# Amplifiers.net
KiCad netlist of a schematic drawn in Altium Designer
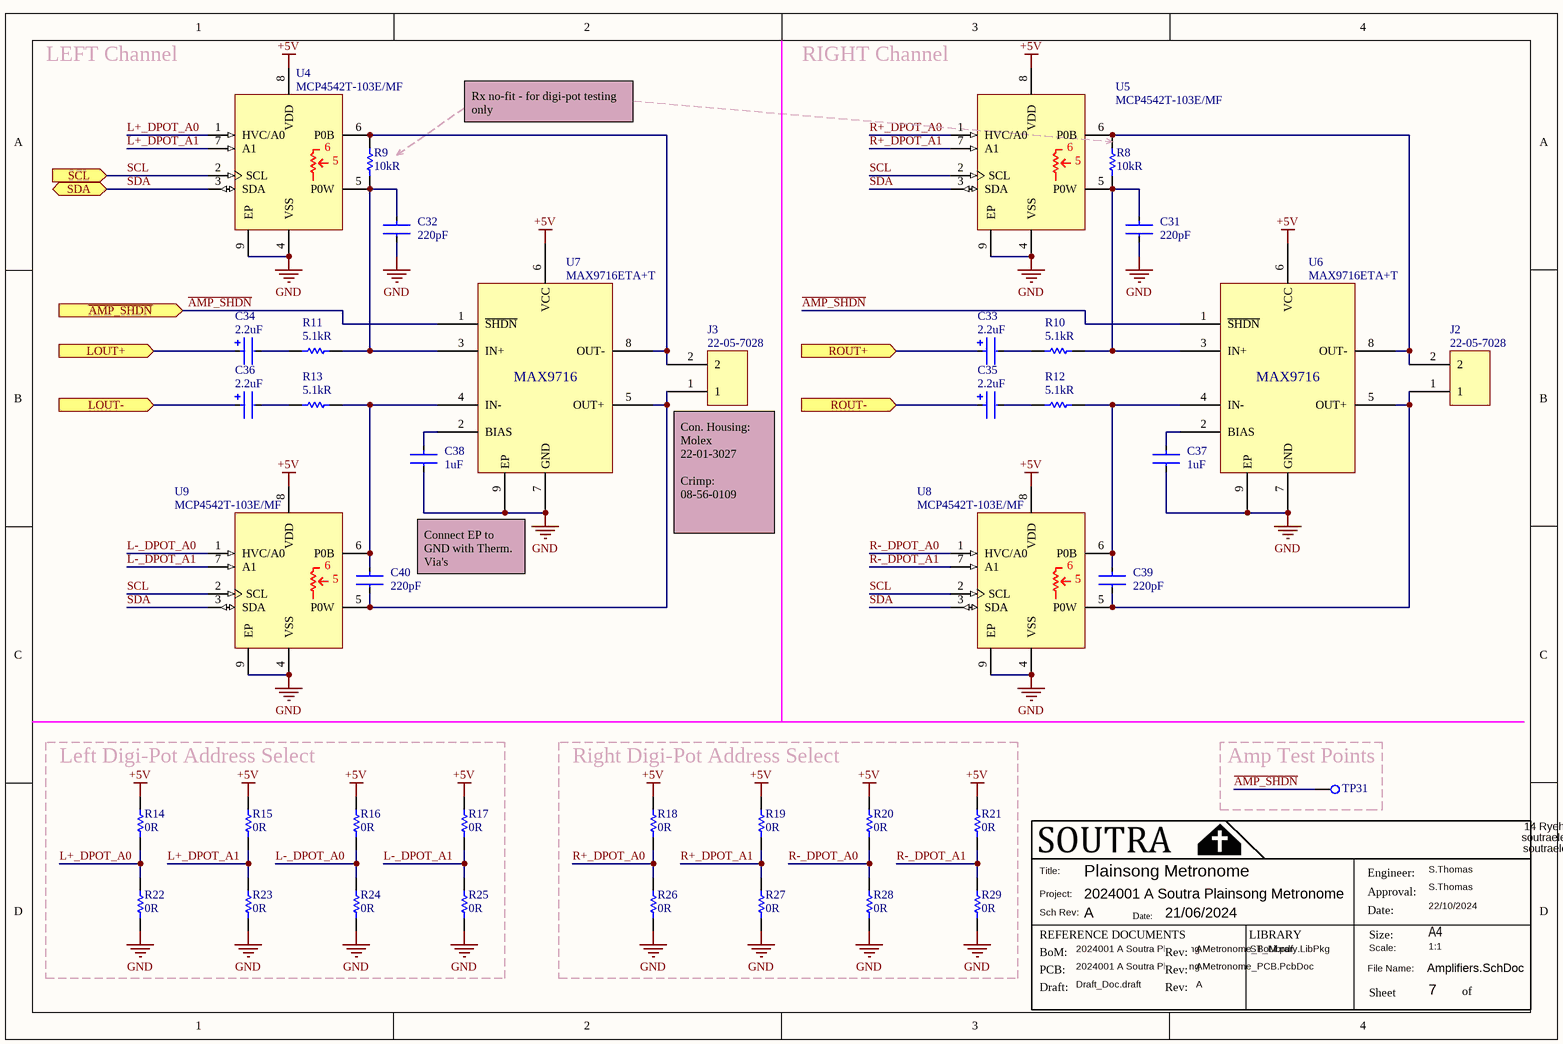
[diagram p0: Amplifiers.SchDoc]

(export (version "E")
  (design (tool "Eeschema 10.0.6"))
  (components
    (comp (ref "C31")
      (value "220pF")
      (footprint "CAPC1005X06L")
      (fields
        (field (name "MANUFACTURER") "Yageo")
        (field (name "MANUFACTURER PART NUMBER") "CC0402KPX7R9BB221")
        (field (name "ALTERNATIVE PART") "MC0402B221K500CT")
      )
      (libsource (lib "ST_Library") (part "CC0402KPX7R9BB221"))
    )
    (comp (ref "C32")
      (value "220pF")
      (footprint "CAPC1005X06L")
      (fields
        (field (name "MANUFACTURER") "Yageo")
        (field (name "MANUFACTURER PART NUMBER") "CC0402KPX7R9BB221")
        (field (name "ALTERNATIVE PART") "MC0402B221K500CT")
      )
      (libsource (lib "ST_Library") (part "CC0402KPX7R9BB221"))
    )
    (comp (ref "C33")
      (value "2.2uF")
      (footprint "CAPC2113X120X50ML20T30")
      (description "Surface Mount Tantalum Capacitor, 2.2 µF, 16 V, 0805 [2012 Metric], ± 10%, 6.5 ohm, R")
      (fields
        (field (name "MANUFACTURER") "AVX Interconnect / Elco")
        (field (name "PART NUMBER") "TAJR225K016RNJ")
      )
      (libsource (lib "ST_Library") (part "TAJR225K016RNJ"))
    )
    (comp (ref "C34")
      (value "2.2uF")
      (footprint "CAPC2113X120X50ML20T30")
      (description "Surface Mount Tantalum Capacitor, 2.2 µF, 16 V, 0805 [2012 Metric], ± 10%, 6.5 ohm, R")
      (fields
        (field (name "MANUFACTURER") "AVX Interconnect / Elco")
        (field (name "PART NUMBER") "TAJR225K016RNJ")
      )
      (libsource (lib "ST_Library") (part "TAJR225K016RNJ"))
    )
    (comp (ref "C35")
      (value "2.2uF")
      (footprint "CAPC2113X120X50ML20T30")
      (description "Surface Mount Tantalum Capacitor, 2.2 µF, 16 V, 0805 [2012 Metric], ± 10%, 6.5 ohm, R")
      (fields
        (field (name "MANUFACTURER") "AVX Interconnect / Elco")
        (field (name "PART NUMBER") "TAJR225K016RNJ")
      )
      (libsource (lib "ST_Library") (part "TAJR225K016RNJ"))
    )
    (comp (ref "C36")
      (value "2.2uF")
      (footprint "CAPC2113X120X50ML20T30")
      (description "Surface Mount Tantalum Capacitor, 2.2 µF, 16 V, 0805 [2012 Metric], ± 10%, 6.5 ohm, R")
      (fields
        (field (name "MANUFACTURER") "AVX Interconnect / Elco")
        (field (name "PART NUMBER") "TAJR225K016RNJ")
      )
      (libsource (lib "ST_Library") (part "TAJR225K016RNJ"))
    )
    (comp (ref "C37")
      (value "1uF")
      (footprint "CAPC1005X06L")
      (fields
        (field (name "MANUFACTURER") "Yageo")
        (field (name "MANUFACTURER PART NUMBER") "CC0402KRX5R6BB105")
        (field (name "ALTERNATIVE PART") "0402ZD105KAT2A")
      )
      (libsource (lib "ST_Library") (part "CC0402KRX5R6BB105"))
    )
    (comp (ref "C38")
      (value "1uF")
      (footprint "CAPC1005X06L")
      (fields
        (field (name "MANUFACTURER") "Yageo")
        (field (name "MANUFACTURER PART NUMBER") "CC0402KRX5R6BB105")
        (field (name "ALTERNATIVE PART") "0402ZD105KAT2A")
      )
      (libsource (lib "ST_Library") (part "CC0402KRX5R6BB105"))
    )
    (comp (ref "C39")
      (value "220pF")
      (footprint "CAPC1005X06L")
      (fields
        (field (name "MANUFACTURER") "Yageo")
        (field (name "MANUFACTURER PART NUMBER") "CC0402KPX7R9BB221")
        (field (name "ALTERNATIVE PART") "MC0402B221K500CT")
      )
      (libsource (lib "ST_Library") (part "CC0402KPX7R9BB221"))
    )
    (comp (ref "C40")
      (value "220pF")
      (footprint "CAPC1005X06L")
      (fields
        (field (name "MANUFACTURER") "Yageo")
        (field (name "MANUFACTURER PART NUMBER") "CC0402KPX7R9BB221")
        (field (name "ALTERNATIVE PART") "MC0402B221K500CT")
      )
      (libsource (lib "ST_Library") (part "CC0402KPX7R9BB221"))
    )
    (comp (ref "J2")
      (value "22-05-7028")
      (footprint "J_MOLEX_22-05-7028")
      (fields (field (name "MANUFACTURER") "Molex"))
      (libsource (lib "ST_Library") (part "22-05-7028"))
    )
    (comp (ref "J3")
      (value "22-05-7028")
      (footprint "J_MOLEX_22-05-7028")
      (fields (field (name "MANUFACTURER") "Molex"))
      (libsource (lib "ST_Library") (part "22-05-7028"))
    )
    (comp (ref "R8")
      (value "10kR")
      (footprint "RESC_0805_2013X50X30LL20T20")
      (fields
        (field (name "MANUFACTURER") "Yageo")
        (field (name "MANUFACTURER PART NUMBER") "RC0805JR-0710KL")
        (field (name "TOLERANCE") "5%")
      )
      (libsource (lib "ST_Library") (part "RC0805JR-0710KL"))
    )
    (comp (ref "R9")
      (value "10kR")
      (footprint "RESC_0805_2013X50X30LL20T20")
      (fields
        (field (name "MANUFACTURER") "Yageo")
        (field (name "MANUFACTURER PART NUMBER") "RC0805JR-0710KL")
        (field (name "TOLERANCE") "5%")
      )
      (libsource (lib "ST_Library") (part "RC0805JR-0710KL"))
    )
    (comp (ref "R10")
      (value "5.1kR")
      (footprint "RESC_0603_1608X06L")
      (description "Fixed Resistor, 0.1W, 5100ohm, 75V, 5% +/-Tol, 100ppm/Cel, Surface Mount, 0603")
      (fields
        (field (name "MANUFACTURER") "Multicomp")
        (field (name "MANUFACTURER PART NUMBER") "MCMR06X512JTL")
      )
      (libsource (lib "ST_Library") (part "MCMR06X512JTL"))
    )
    (comp (ref "R11")
      (value "5.1kR")
      (footprint "RESC_0603_1608X06L")
      (description "Fixed Resistor, 0.1W, 5100ohm, 75V, 5% +/-Tol, 100ppm/Cel, Surface Mount, 0603")
      (fields
        (field (name "MANUFACTURER") "Multicomp")
        (field (name "MANUFACTURER PART NUMBER") "MCMR06X512JTL")
      )
      (libsource (lib "ST_Library") (part "MCMR06X512JTL"))
    )
    (comp (ref "R12")
      (value "5.1kR")
      (footprint "RESC_0603_1608X06L")
      (description "Fixed Resistor, 0.1W, 5100ohm, 75V, 5% +/-Tol, 100ppm/Cel, Surface Mount, 0603")
      (fields
        (field (name "MANUFACTURER") "Multicomp")
        (field (name "MANUFACTURER PART NUMBER") "MCMR06X512JTL")
      )
      (libsource (lib "ST_Library") (part "MCMR06X512JTL"))
    )
    (comp (ref "R13")
      (value "5.1kR")
      (footprint "RESC_0603_1608X06L")
      (description "Fixed Resistor, 0.1W, 5100ohm, 75V, 5% +/-Tol, 100ppm/Cel, Surface Mount, 0603")
      (fields
        (field (name "MANUFACTURER") "Multicomp")
        (field (name "MANUFACTURER PART NUMBER") "MCMR06X512JTL")
      )
      (libsource (lib "ST_Library") (part "MCMR06X512JTL"))
    )
    (comp (ref "R14")
      (value "0R")
      (footprint "RESC_0603_1608X06L")
      (description "Fixed Resistor, Metal Glaze/thick Film, 0.063W, 0ohm, 1% +/-Tol, Surface Mount, 0603")
      (fields
        (field (name "MANUFACTURER") "Multicomp")
        (field (name "MANUFACTURER PART NUMBER") "MC0063W06030R")
      )
      (libsource (lib "ST_Library") (part "MC0063W06030R"))
    )
    (comp (ref "R15")
      (value "0R")
      (footprint "RESC_0603_1608X06L")
      (description "Fixed Resistor, Metal Glaze/thick Film, 0.063W, 0ohm, 1% +/-Tol, Surface Mount, 0603")
      (fields
        (field (name "MANUFACTURER") "Multicomp")
        (field (name "MANUFACTURER PART NUMBER") "MC0063W06030R")
      )
      (libsource (lib "ST_Library") (part "MC0063W06030R"))
    )
    (comp (ref "R16")
      (value "0R")
      (footprint "RESC_0603_1608X06L")
      (description "Fixed Resistor, Metal Glaze/thick Film, 0.063W, 0ohm, 1% +/-Tol, Surface Mount, 0603")
      (fields
        (field (name "MANUFACTURER") "Multicomp")
        (field (name "MANUFACTURER PART NUMBER") "MC0063W06030R")
      )
      (libsource (lib "ST_Library") (part "MC0063W06030R"))
    )
    (comp (ref "R17")
      (value "0R")
      (footprint "RESC_0603_1608X06L")
      (description "Fixed Resistor, Metal Glaze/thick Film, 0.063W, 0ohm, 1% +/-Tol, Surface Mount, 0603")
      (fields
        (field (name "MANUFACTURER") "Multicomp")
        (field (name "MANUFACTURER PART NUMBER") "MC0063W06030R")
      )
      (libsource (lib "ST_Library") (part "MC0063W06030R"))
    )
    (comp (ref "R18")
      (value "0R")
      (footprint "RESC_0603_1608X06L")
      (description "Fixed Resistor, Metal Glaze/thick Film, 0.063W, 0ohm, 1% +/-Tol, Surface Mount, 0603")
      (fields
        (field (name "MANUFACTURER") "Multicomp")
        (field (name "MANUFACTURER PART NUMBER") "MC0063W06030R")
      )
      (libsource (lib "ST_Library") (part "MC0063W06030R"))
    )
    (comp (ref "R19")
      (value "0R")
      (footprint "RESC_0603_1608X06L")
      (description "Fixed Resistor, Metal Glaze/thick Film, 0.063W, 0ohm, 1% +/-Tol, Surface Mount, 0603")
      (fields
        (field (name "MANUFACTURER") "Multicomp")
        (field (name "MANUFACTURER PART NUMBER") "MC0063W06030R")
      )
      (libsource (lib "ST_Library") (part "MC0063W06030R"))
    )
    (comp (ref "R20")
      (value "0R")
      (footprint "RESC_0603_1608X06L")
      (description "Fixed Resistor, Metal Glaze/thick Film, 0.063W, 0ohm, 1% +/-Tol, Surface Mount, 0603")
      (fields
        (field (name "MANUFACTURER") "Multicomp")
        (field (name "MANUFACTURER PART NUMBER") "MC0063W06030R")
      )
      (libsource (lib "ST_Library") (part "MC0063W06030R"))
    )
    (comp (ref "R21")
      (value "0R")
      (footprint "RESC_0603_1608X06L")
      (description "Fixed Resistor, Metal Glaze/thick Film, 0.063W, 0ohm, 1% +/-Tol, Surface Mount, 0603")
      (fields
        (field (name "MANUFACTURER") "Multicomp")
        (field (name "MANUFACTURER PART NUMBER") "MC0063W06030R")
      )
      (libsource (lib "ST_Library") (part "MC0063W06030R"))
    )
    (comp (ref "R22")
      (value "0R")
      (footprint "RESC_0603_1608X06L")
      (description "Fixed Resistor, Metal Glaze/thick Film, 0.063W, 0ohm, 1% +/-Tol, Surface Mount, 0603")
      (fields
        (field (name "MANUFACTURER") "Multicomp")
        (field (name "MANUFACTURER PART NUMBER") "MC0063W06030R")
      )
      (libsource (lib "ST_Library") (part "MC0063W06030R"))
    )
    (comp (ref "R23")
      (value "0R")
      (footprint "RESC_0603_1608X06L")
      (description "Fixed Resistor, Metal Glaze/thick Film, 0.063W, 0ohm, 1% +/-Tol, Surface Mount, 0603")
      (fields
        (field (name "MANUFACTURER") "Multicomp")
        (field (name "MANUFACTURER PART NUMBER") "MC0063W06030R")
      )
      (libsource (lib "ST_Library") (part "MC0063W06030R"))
    )
    (comp (ref "R24")
      (value "0R")
      (footprint "RESC_0603_1608X06L")
      (description "Fixed Resistor, Metal Glaze/thick Film, 0.063W, 0ohm, 1% +/-Tol, Surface Mount, 0603")
      (fields
        (field (name "MANUFACTURER") "Multicomp")
        (field (name "MANUFACTURER PART NUMBER") "MC0063W06030R")
      )
      (libsource (lib "ST_Library") (part "MC0063W06030R"))
    )
    (comp (ref "R25")
      (value "0R")
      (footprint "RESC_0603_1608X06L")
      (description "Fixed Resistor, Metal Glaze/thick Film, 0.063W, 0ohm, 1% +/-Tol, Surface Mount, 0603")
      (fields
        (field (name "MANUFACTURER") "Multicomp")
        (field (name "MANUFACTURER PART NUMBER") "MC0063W06030R")
      )
      (libsource (lib "ST_Library") (part "MC0063W06030R"))
    )
    (comp (ref "R26")
      (value "0R")
      (footprint "RESC_0603_1608X06L")
      (description "Fixed Resistor, Metal Glaze/thick Film, 0.063W, 0ohm, 1% +/-Tol, Surface Mount, 0603")
      (fields
        (field (name "MANUFACTURER") "Multicomp")
        (field (name "MANUFACTURER PART NUMBER") "MC0063W06030R")
      )
      (libsource (lib "ST_Library") (part "MC0063W06030R"))
    )
    (comp (ref "R27")
      (value "0R")
      (footprint "RESC_0603_1608X06L")
      (description "Fixed Resistor, Metal Glaze/thick Film, 0.063W, 0ohm, 1% +/-Tol, Surface Mount, 0603")
      (fields
        (field (name "MANUFACTURER") "Multicomp")
        (field (name "MANUFACTURER PART NUMBER") "MC0063W06030R")
      )
      (libsource (lib "ST_Library") (part "MC0063W06030R"))
    )
    (comp (ref "R28")
      (value "0R")
      (footprint "RESC_0603_1608X06L")
      (description "Fixed Resistor, Metal Glaze/thick Film, 0.063W, 0ohm, 1% +/-Tol, Surface Mount, 0603")
      (fields
        (field (name "MANUFACTURER") "Multicomp")
        (field (name "MANUFACTURER PART NUMBER") "MC0063W06030R")
      )
      (libsource (lib "ST_Library") (part "MC0063W06030R"))
    )
    (comp (ref "R29")
      (value "0R")
      (footprint "RESC_0603_1608X06L")
      (description "Fixed Resistor, Metal Glaze/thick Film, 0.063W, 0ohm, 1% +/-Tol, Surface Mount, 0603")
      (fields
        (field (name "MANUFACTURER") "Multicomp")
        (field (name "MANUFACTURER PART NUMBER") "MC0063W06030R")
      )
      (libsource (lib "ST_Library") (part "MC0063W06030R"))
    )
    (comp (ref "TP31")
      (value "TP_CIRCLE_R1")
      (footprint "TP_CIRCLE_R1")
      (description "Test Point, SMD, Circular, Radius = 1mm")
      (libsource (lib "ST_Library") (part "TP_CIRCLE_R1"))
    )
    (comp (ref "U4")
      (value "MCP4542T-103E/MF")
      (footprint "DFN-MF8")
      (fields (field (name "MANUFACTURER") "Microchip"))
      (libsource (lib "ST_Library") (part "MCP4542T-103E/MF"))
    )
    (comp (ref "U5")
      (value "MCP4542T-103E/MF")
      (footprint "DFN-MF8")
      (fields (field (name "MANUFACTURER") "Microchip"))
      (libsource (lib "ST_Library") (part "MCP4542T-103E/MF"))
    )
    (comp (ref "U6")
      (value "MAX9716ETA+T")
      (footprint "TDFN300X300X80_HS-9L")
      (description "Audio Amplifier, 1.4W, 1 Channel(s), 1 Func, BICMOS")
      (fields (field (name "MANUFACTURER") "Maxim"))
      (libsource (lib "ST_Library") (part "MAX9716ETA+T"))
    )
    (comp (ref "U7")
      (value "MAX9716ETA+T")
      (footprint "TDFN300X300X80_HS-9L")
      (description "Audio Amplifier, 1.4W, 1 Channel(s), 1 Func, BICMOS")
      (fields (field (name "MANUFACTURER") "Maxim"))
      (libsource (lib "ST_Library") (part "MAX9716ETA+T"))
    )
    (comp (ref "U8")
      (value "MCP4542T-103E/MF")
      (footprint "DFN-MF8")
      (fields (field (name "MANUFACTURER") "Microchip"))
      (libsource (lib "ST_Library") (part "MCP4542T-103E/MF"))
    )
    (comp (ref "U9")
      (value "MCP4542T-103E/MF")
      (footprint "DFN-MF8")
      (fields (field (name "MANUFACTURER") "Microchip"))
      (libsource (lib "ST_Library") (part "MCP4542T-103E/MF"))
    )
  )
  (nets
    (net (code "1") (name "+5V") (class "Default")
      (node (ref "R14") (pin "2") (pinfunction "2_2") (pintype "passive"))
      (node (ref "R15") (pin "2") (pinfunction "2_2") (pintype "passive"))
      (node (ref "R16") (pin "2") (pinfunction "2_2") (pintype "passive"))
      (node (ref "R17") (pin "2") (pinfunction "2_2") (pintype "passive"))
      (node (ref "R18") (pin "2") (pinfunction "2_2") (pintype "passive"))
      (node (ref "R19") (pin "2") (pinfunction "2_2") (pintype "passive"))
      (node (ref "R20") (pin "2") (pinfunction "2_2") (pintype "passive"))
      (node (ref "R21") (pin "2") (pinfunction "2_2") (pintype "passive"))
      (node (ref "U4") (pin "8") (pinfunction "VDD_8") (pintype "power_in"))
      (node (ref "U5") (pin "8") (pinfunction "VDD_8") (pintype "power_in"))
      (node (ref "U6") (pin "6") (pinfunction "VCC_6") (pintype "passive"))
      (node (ref "U7") (pin "6") (pinfunction "VCC_6") (pintype "passive"))
      (node (ref "U8") (pin "8") (pinfunction "VDD_8") (pintype "power_in"))
      (node (ref "U9") (pin "8") (pinfunction "VDD_8") (pintype "power_in"))
    )
    (net (code "2") (name "/L+_DPOT_A0") (class "Default")
      (node (ref "R14") (pin "1") (pinfunction "1_1") (pintype "passive"))
      (node (ref "R22") (pin "2") (pinfunction "2_2") (pintype "passive"))
      (node (ref "U4") (pin "1") (pinfunction "HVC/A0_1") (pintype "input"))
    )
    (net (code "3") (name "/L+_DPOT_A1") (class "Default")
      (node (ref "R15") (pin "1") (pinfunction "1_1") (pintype "passive"))
      (node (ref "R23") (pin "2") (pinfunction "2_2") (pintype "passive"))
      (node (ref "U4") (pin "7") (pinfunction "A1_7") (pintype "input"))
    )
    (net (code "4") (name "/L-_DPOT_A0") (class "Default")
      (node (ref "R16") (pin "1") (pinfunction "1_1") (pintype "passive"))
      (node (ref "R24") (pin "2") (pinfunction "2_2") (pintype "passive"))
      (node (ref "U9") (pin "1") (pinfunction "HVC/A0_1") (pintype "input"))
    )
    (net (code "5") (name "/L-_DPOT_A1") (class "Default")
      (node (ref "R17") (pin "1") (pinfunction "1_1") (pintype "passive"))
      (node (ref "R25") (pin "2") (pinfunction "2_2") (pintype "passive"))
      (node (ref "U9") (pin "7") (pinfunction "A1_7") (pintype "input"))
    )
    (net (code "6") (name "/LOUT+") (class "Default")
      (node (ref "C34") (pin "1") (pinfunction "1_1") (pintype "passive"))
    )
    (net (code "7") (name "/LOUT-") (class "Default")
      (node (ref "C36") (pin "1") (pinfunction "1_1") (pintype "passive"))
    )
    (net (code "8") (name "/R+_DPOT_A0") (class "Default")
      (node (ref "R18") (pin "1") (pinfunction "1_1") (pintype "passive"))
      (node (ref "R26") (pin "2") (pinfunction "2_2") (pintype "passive"))
      (node (ref "U5") (pin "1") (pinfunction "HVC/A0_1") (pintype "input"))
    )
    (net (code "9") (name "/R+_DPOT_A1") (class "Default")
      (node (ref "R19") (pin "1") (pinfunction "1_1") (pintype "passive"))
      (node (ref "R27") (pin "2") (pinfunction "2_2") (pintype "passive"))
      (node (ref "U5") (pin "7") (pinfunction "A1_7") (pintype "input"))
    )
    (net (code "10") (name "/R-_DPOT_A0") (class "Default")
      (node (ref "R20") (pin "1") (pinfunction "1_1") (pintype "passive"))
      (node (ref "R28") (pin "2") (pinfunction "2_2") (pintype "passive"))
      (node (ref "U8") (pin "1") (pinfunction "HVC/A0_1") (pintype "input"))
    )
    (net (code "11") (name "/R-_DPOT_A1") (class "Default")
      (node (ref "R21") (pin "1") (pinfunction "1_1") (pintype "passive"))
      (node (ref "R29") (pin "2") (pinfunction "2_2") (pintype "passive"))
      (node (ref "U8") (pin "7") (pinfunction "A1_7") (pintype "input"))
    )
    (net (code "12") (name "/ROUT+") (class "Default")
      (node (ref "C33") (pin "1") (pinfunction "1_1") (pintype "passive"))
    )
    (net (code "13") (name "/ROUT-") (class "Default")
      (node (ref "C35") (pin "1") (pinfunction "1_1") (pintype "passive"))
    )
    (net (code "14") (name "/SCL") (class "Default")
      (node (ref "U4") (pin "2") (pinfunction "SCL_2") (pintype "input"))
      (node (ref "U5") (pin "2") (pinfunction "SCL_2") (pintype "input"))
      (node (ref "U8") (pin "2") (pinfunction "SCL_2") (pintype "input"))
      (node (ref "U9") (pin "2") (pinfunction "SCL_2") (pintype "input"))
    )
    (net (code "15") (name "/SDA") (class "Default")
      (node (ref "U4") (pin "3") (pinfunction "SDA_3") (pintype "bidirectional"))
      (node (ref "U5") (pin "3") (pinfunction "SDA_3") (pintype "bidirectional"))
      (node (ref "U8") (pin "3") (pinfunction "SDA_3") (pintype "bidirectional"))
      (node (ref "U9") (pin "3") (pinfunction "SDA_3") (pintype "bidirectional"))
    )
    (net (code "16") (name "/~{AMP_SHDN}") (class "Default")
      (node (ref "TP31") (pin "1") (pinfunction "1_1") (pintype "passive"))
      (node (ref "U6") (pin "1") (pinfunction "~{SHDN}_1") (pintype "passive"))
      (node (ref "U7") (pin "1") (pinfunction "~{SHDN}_1") (pintype "passive"))
    )
    (net (code "17") (name "GND") (class "Default")
      (node (ref "C31") (pin "2") (pinfunction "2_2") (pintype "passive"))
      (node (ref "C32") (pin "2") (pinfunction "2_2") (pintype "passive"))
      (node (ref "C37") (pin "2") (pinfunction "2_2") (pintype "passive"))
      (node (ref "C38") (pin "2") (pinfunction "2_2") (pintype "passive"))
      (node (ref "R22") (pin "1") (pinfunction "1_1") (pintype "passive"))
      (node (ref "R23") (pin "1") (pinfunction "1_1") (pintype "passive"))
      (node (ref "R24") (pin "1") (pinfunction "1_1") (pintype "passive"))
      (node (ref "R25") (pin "1") (pinfunction "1_1") (pintype "passive"))
      (node (ref "R26") (pin "1") (pinfunction "1_1") (pintype "passive"))
      (node (ref "R27") (pin "1") (pinfunction "1_1") (pintype "passive"))
      (node (ref "R28") (pin "1") (pinfunction "1_1") (pintype "passive"))
      (node (ref "R29") (pin "1") (pinfunction "1_1") (pintype "passive"))
      (node (ref "U4") (pin "4") (pinfunction "VSS_4") (pintype "power_in"))
      (node (ref "U4") (pin "9") (pinfunction "EP_9") (pintype "passive"))
      (node (ref "U5") (pin "4") (pinfunction "VSS_4") (pintype "power_in"))
      (node (ref "U5") (pin "9") (pinfunction "EP_9") (pintype "passive"))
      (node (ref "U6") (pin "7") (pinfunction "GND_7") (pintype "passive"))
      (node (ref "U6") (pin "9") (pinfunction "EP_9") (pintype "passive"))
      (node (ref "U7") (pin "7") (pinfunction "GND_7") (pintype "passive"))
      (node (ref "U7") (pin "9") (pinfunction "EP_9") (pintype "passive"))
      (node (ref "U8") (pin "4") (pinfunction "VSS_4") (pintype "power_in"))
      (node (ref "U8") (pin "9") (pinfunction "EP_9") (pintype "passive"))
      (node (ref "U9") (pin "4") (pinfunction "VSS_4") (pintype "power_in"))
      (node (ref "U9") (pin "9") (pinfunction "EP_9") (pintype "passive"))
    )
    (net (code "18") (name "Net-(C33-Pad2)") (class "Default")
      (node (ref "C33") (pin "2") (pinfunction "2_2") (pintype "passive"))
      (node (ref "R10") (pin "1") (pinfunction "1_1") (pintype "passive"))
    )
    (net (code "19") (name "Net-(C34-Pad2)") (class "Default")
      (node (ref "C34") (pin "2") (pinfunction "2_2") (pintype "passive"))
      (node (ref "R11") (pin "1") (pinfunction "1_1") (pintype "passive"))
    )
    (net (code "20") (name "Net-(C35-Pad2)") (class "Default")
      (node (ref "C35") (pin "2") (pinfunction "2_2") (pintype "passive"))
      (node (ref "R12") (pin "1") (pinfunction "1_1") (pintype "passive"))
    )
    (net (code "21") (name "Net-(C36-Pad2)") (class "Default")
      (node (ref "C36") (pin "2") (pinfunction "2_2") (pintype "passive"))
      (node (ref "R13") (pin "1") (pinfunction "1_1") (pintype "passive"))
    )
    (net (code "22") (name "Net-(U4-P0B)") (class "Default")
      (node (ref "J3") (pin "2") (pinfunction "2_2") (pintype "passive"))
      (node (ref "R9") (pin "2") (pinfunction "2_2") (pintype "passive"))
      (node (ref "U4") (pin "6") (pinfunction "P0B_6") (pintype "passive"))
      (node (ref "U7") (pin "8") (pinfunction "OUT-_8") (pintype "passive"))
    )
    (net (code "23") (name "Net-(U4-P0W)") (class "Default")
      (node (ref "C32") (pin "1") (pinfunction "1_1") (pintype "passive"))
      (node (ref "R11") (pin "2") (pinfunction "2_2") (pintype "passive"))
      (node (ref "R9") (pin "1") (pinfunction "1_1") (pintype "passive"))
      (node (ref "U4") (pin "5") (pinfunction "P0W_5") (pintype "passive"))
      (node (ref "U7") (pin "3") (pinfunction "IN+_3") (pintype "passive"))
    )
    (net (code "24") (name "Net-(U5-P0B)") (class "Default")
      (node (ref "J2") (pin "2") (pinfunction "2_2") (pintype "passive"))
      (node (ref "R8") (pin "2") (pinfunction "2_2") (pintype "passive"))
      (node (ref "U5") (pin "6") (pinfunction "P0B_6") (pintype "passive"))
      (node (ref "U6") (pin "8") (pinfunction "OUT-_8") (pintype "passive"))
    )
    (net (code "25") (name "Net-(U5-P0W)") (class "Default")
      (node (ref "C31") (pin "1") (pinfunction "1_1") (pintype "passive"))
      (node (ref "R10") (pin "2") (pinfunction "2_2") (pintype "passive"))
      (node (ref "R8") (pin "1") (pinfunction "1_1") (pintype "passive"))
      (node (ref "U5") (pin "5") (pinfunction "P0W_5") (pintype "passive"))
      (node (ref "U6") (pin "3") (pinfunction "IN+_3") (pintype "passive"))
    )
    (net (code "26") (name "Net-(U6-BIAS)") (class "Default")
      (node (ref "C37") (pin "1") (pinfunction "1_1") (pintype "passive"))
      (node (ref "U6") (pin "2") (pinfunction "BIAS_2") (pintype "passive"))
    )
    (net (code "27") (name "Net-(U6-IN-)") (class "Default")
      (node (ref "C39") (pin "1") (pinfunction "1_1") (pintype "passive"))
      (node (ref "R12") (pin "2") (pinfunction "2_2") (pintype "passive"))
      (node (ref "U6") (pin "4") (pinfunction "IN-_4") (pintype "passive"))
      (node (ref "U8") (pin "6") (pinfunction "P0B_6") (pintype "passive"))
    )
    (net (code "28") (name "Net-(U6-OUT+)") (class "Default")
      (node (ref "C39") (pin "2") (pinfunction "2_2") (pintype "passive"))
      (node (ref "J2") (pin "1") (pinfunction "1_1") (pintype "passive"))
      (node (ref "U6") (pin "5") (pinfunction "OUT+_5") (pintype "passive"))
      (node (ref "U8") (pin "5") (pinfunction "P0W_5") (pintype "passive"))
    )
    (net (code "29") (name "Net-(U7-BIAS)") (class "Default")
      (node (ref "C38") (pin "1") (pinfunction "1_1") (pintype "passive"))
      (node (ref "U7") (pin "2") (pinfunction "BIAS_2") (pintype "passive"))
    )
    (net (code "30") (name "Net-(U7-IN-)") (class "Default")
      (node (ref "C40") (pin "1") (pinfunction "1_1") (pintype "passive"))
      (node (ref "R13") (pin "2") (pinfunction "2_2") (pintype "passive"))
      (node (ref "U7") (pin "4") (pinfunction "IN-_4") (pintype "passive"))
      (node (ref "U9") (pin "6") (pinfunction "P0B_6") (pintype "passive"))
    )
    (net (code "31") (name "Net-(U7-OUT+)") (class "Default")
      (node (ref "C40") (pin "2") (pinfunction "2_2") (pintype "passive"))
      (node (ref "J3") (pin "1") (pinfunction "1_1") (pintype "passive"))
      (node (ref "U7") (pin "5") (pinfunction "OUT+_5") (pintype "passive"))
      (node (ref "U9") (pin "5") (pinfunction "P0W_5") (pintype "passive"))
    )
  )
)
